# tof.net
KiCad netlist of a schematic drawn in Altium Designer
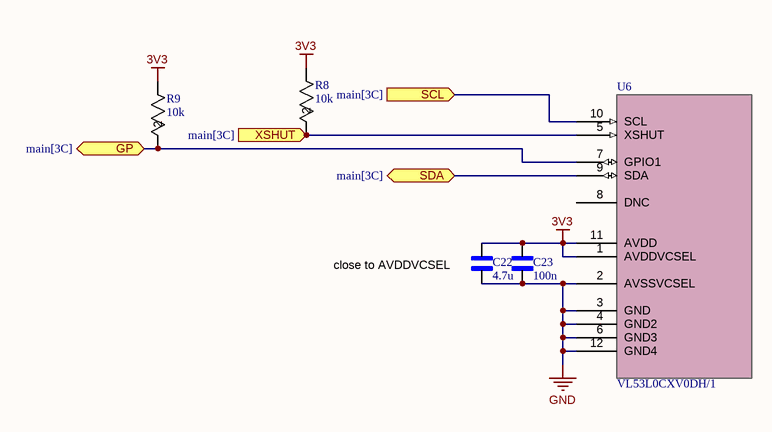
[diagram p0: tof.SchDoc]

(export (version "E")
  (design (tool "Eeschema 10.0.6"))
  (components
    (comp (ref "C22")
      (value "4.7u")
      (footprint "CAPC1005X55N:CAPC1005X55N")
      (description "CAP CER 4.7UF 6.3V X5R 0402")
      (fields (field (name "MF") "{'manufacturer': u'Taiyo Yuden'}") (field (name "MP") "GRM155R60J475M"))
      (libsource (lib "UMK105B7104KVHF") (part "GRM155R60J475M"))
    )
    (comp (ref "C23")
      (value "100n")
      (footprint "CAPC1005X55N:CAPC1005X55N")
      (description "CAP CER 0.1UF 50V X7R 0402")
      (fields (field (name "MF") "{'manufacturer': u'Taiyo Yuden'}") (field (name "MP") "UMK105B7104KVHF"))
      (libsource (lib "UMK105B7104KVHF") (part "UMK105B7104KVHF"))
    )
    (comp (ref "R8")
      (value "10k")
      (footprint "RT0603BRE07475RL:RC0603N_YAG")
      (description "10K OHM 0.1% 1/10W 0603")
      (fields
        (field (name "MANUFACTURER_PART_NUMBER") "RT0603BRD0710KL")
        (field (name "COPYRIGHT") "Copyright (C) 2026 Ultra Librarian. All rights reserved.")
      )
      (libsource (lib "RT0603BRE07475RL") (part "RT0603BRD0710KL"))
    )
    (comp (ref "R9")
      (value "10k")
      (footprint "RT0603BRE07475RL:RC0603N_YAG")
      (description "10K OHM 0.1% 1/10W 0603")
      (fields
        (field (name "MANUFACTURER_PART_NUMBER") "RT0603BRD0710KL")
        (field (name "COPYRIGHT") "Copyright (C) 2026 Ultra Librarian. All rights reserved.")
      )
      (libsource (lib "RT0603BRE07475RL") (part "RT0603BRD0710KL"))
    )
    (comp (ref "U6")
      (value "VL53L0CXV0DH/1")
      (footprint "LGA12_STM")
      (description "Time-of-Flight (ToF) ranging sensor")
      (fields (field (name "COPYRIGHT") "Copyright (C) 2026 Ultra Librarian. All rights reserved."))
      (libsource (lib "VL53L0CXV0DH1") (part "VL53L0CXV0DH1"))
    )
  )
  (nets
    (net (code "1") (name "/GP") (class "Default")
      (node (ref "R9") (pin "2") (pinfunction "2_2") (pintype "passive"))
      (node (ref "U6") (pin "7") (pinfunction "GPIO1_7") (pintype "bidirectional"))
    )
    (net (code "2") (name "/SCL") (class "Default")
      (node (ref "U6") (pin "10") (pinfunction "SCL_10") (pintype "input"))
    )
    (net (code "3") (name "/SDA") (class "Default")
      (node (ref "U6") (pin "9") (pinfunction "SDA_9") (pintype "bidirectional"))
    )
    (net (code "4") (name "/XSHUT") (class "Default")
      (node (ref "R8") (pin "2") (pinfunction "2_2") (pintype "passive"))
      (node (ref "U6") (pin "5") (pinfunction "XSHUT_5") (pintype "input"))
    )
    (net (code "5") (name "3V3") (class "Default")
      (node (ref "C22") (pin "2") (pinfunction "2_2") (pintype "passive"))
      (node (ref "C23") (pin "2") (pinfunction "2_2") (pintype "passive"))
      (node (ref "R8") (pin "1") (pinfunction "1_1") (pintype "passive"))
      (node (ref "R9") (pin "1") (pinfunction "1_1") (pintype "passive"))
      (node (ref "U6") (pin "1") (pinfunction "AVDDVCSEL_1") (pintype "power_in"))
      (node (ref "U6") (pin "11") (pinfunction "AVDD_11") (pintype "power_in"))
    )
    (net (code "6") (name "GND") (class "Default")
      (node (ref "C22") (pin "1") (pinfunction "1_1") (pintype "passive"))
      (node (ref "C23") (pin "1") (pinfunction "1_1") (pintype "passive"))
      (node (ref "U6") (pin "12") (pinfunction "GND4_12") (pintype "power_in"))
      (node (ref "U6") (pin "2") (pinfunction "AVSSVCSEL_2") (pintype "power_in"))
      (node (ref "U6") (pin "3") (pinfunction "GND_3") (pintype "power_in"))
      (node (ref "U6") (pin "4") (pinfunction "GND2_4") (pintype "power_in"))
      (node (ref "U6") (pin "6") (pinfunction "GND3_6") (pintype "power_in"))
    )
    (net (code "7") (name "unconnected-(U6-DNC-Pad8)") (class "Default")
      (node (ref "U6") (pin "8") (pinfunction "DNC_8") (pintype "passive"))
    )
  )
)
